# M_C_ext_main_cp2102N.net
KiCad netlist of a schematic drawn in EAGLE
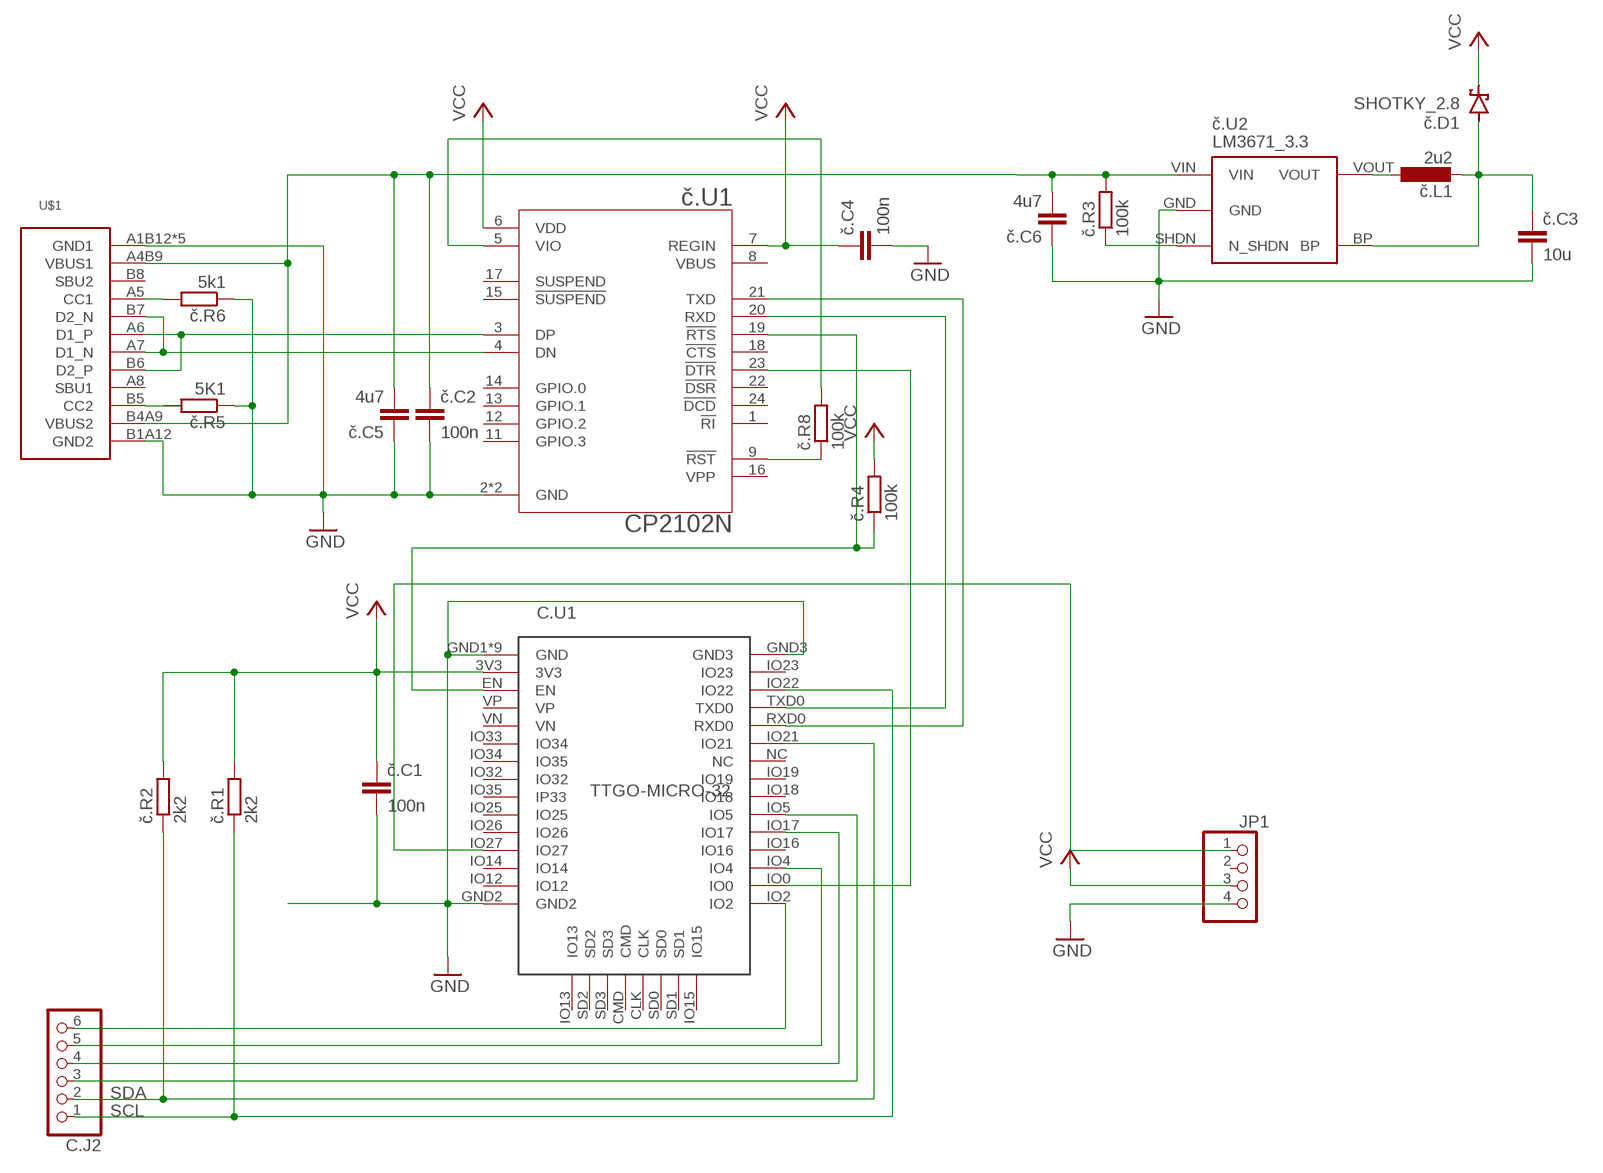
[diagram p0: schematic, sheet 1]

(export (version "E")
  (design (tool "Eeschema 10.0.6"))
  (components
    (comp (ref "C.J2")
      (value "PINHD-1X6")
      (footprint "eagle-import:1X06")
      (libsource (lib "eagle-import") (part "PINHD-1X6"))
    )
    (comp (ref "C.U1")
      (value "TTGO-MICRO-32")
      (footprint "eagle-import:TTGO-MICRO-32")
      (libsource (lib "eagle-import") (part "TTGO-MICRO-32"))
    )
    (comp (ref "JP1")
      (value "PINHD-1X4")
      (footprint "eagle-import:1X04")
      (libsource (lib "eagle-import") (part "PINHD-1X4"))
    )
    (comp (ref "U$1")
      (value "USB-C")
      (footprint "eagle-import:USB-C")
      (libsource (lib "eagle-import") (part "USB-C"))
    )
    (comp (ref "č.C1")
      (value "100n")
      (footprint "eagle-import:C0603")
      (libsource (lib "eagle-import") (part "C-EUC0603"))
    )
    (comp (ref "č.C2")
      (value "100n")
      (footprint "eagle-import:C0603")
      (libsource (lib "eagle-import") (part "C-EUC0603"))
    )
    (comp (ref "č.C3")
      (value "10u")
      (footprint "eagle-import:C0805")
      (libsource (lib "eagle-import") (part "C-EUC0805"))
    )
    (comp (ref "č.C4")
      (value "100n")
      (footprint "eagle-import:C0603")
      (libsource (lib "eagle-import") (part "C-EUC0603"))
    )
    (comp (ref "č.C5")
      (value "4u7")
      (footprint "eagle-import:C0603")
      (libsource (lib "eagle-import") (part "C-EUC0603"))
    )
    (comp (ref "č.C6")
      (value "4u7")
      (footprint "eagle-import:C0603")
      (libsource (lib "eagle-import") (part "C-EUC0603"))
    )
    (comp (ref "č.D1")
      (value "SHOTKY_2.8")
      (footprint "eagle-import:SHOTKY_2.8")
      (libsource (lib "eagle-import") (part "SHOTKY_2.8"))
    )
    (comp (ref "č.L1")
      (value "2u2")
      (footprint "eagle-import:L3230M")
      (libsource (lib "eagle-import") (part "L-EUL3230M"))
    )
    (comp (ref "č.R1")
      (value "2k2")
      (footprint "eagle-import:R0603")
      (libsource (lib "eagle-import") (part "R-EU_R0603"))
    )
    (comp (ref "č.R2")
      (value "2k2")
      (footprint "eagle-import:R0603")
      (libsource (lib "eagle-import") (part "R-EU_R0603"))
    )
    (comp (ref "č.R3")
      (value "100k")
      (footprint "eagle-import:R0603")
      (libsource (lib "eagle-import") (part "R-EU_R0603"))
    )
    (comp (ref "č.R4")
      (value "100k")
      (footprint "eagle-import:R0603")
      (libsource (lib "eagle-import") (part "R-EU_R0603"))
    )
    (comp (ref "č.R5")
      (value "5K1")
      (footprint "eagle-import:R0603")
      (libsource (lib "eagle-import") (part "R-EU_R0603"))
    )
    (comp (ref "č.R6")
      (value "5k1")
      (footprint "eagle-import:R0603")
      (libsource (lib "eagle-import") (part "R-EU_R0603"))
    )
    (comp (ref "č.R8")
      (value "100k")
      (footprint "eagle-import:R0603")
      (libsource (lib "eagle-import") (part "R-EU_R0603"))
    )
    (comp (ref "č.U1")
      (value "CP2102N")
      (footprint "eagle-import:QFN50P400X400X80-25N")
      (fields (field (name "MF") "Silicon Labs") (field (name "MP") "CP2104"))
      (libsource (lib "eagle-import") (part "CP2104-F03-GM"))
    )
    (comp (ref "č.U2")
      (value "LM3671_3.3")
      (footprint "eagle-import:SOT32-5")
      (libsource (lib "eagle-import") (part "STABILISER_APE8865"))
    )
  )
  (nets
    (net (code "1") (name "/SCL") (class "Default")
      (node (ref "C.J2") (pin "1") (pinfunction "1_1") (pintype "passive"))
      (node (ref "C.U1") (pin "IO22") (pinfunction "IO22_IO22") (pintype "bidirectional"))
      (node (ref "č.R1") (pin "1") (pinfunction "1_1") (pintype "passive"))
    )
    (net (code "2") (name "/SDA") (class "Default")
      (node (ref "C.J2") (pin "2") (pinfunction "2_2") (pintype "passive"))
      (node (ref "C.U1") (pin "IO21") (pinfunction "IO21_IO21") (pintype "bidirectional"))
      (node (ref "č.R2") (pin "1") (pinfunction "1_1") (pintype "passive"))
    )
    (net (code "3") (name "GND") (class "Default")
      (node (ref "C.U1") (pin "GND1") (pinfunction "GND_GND1") (pintype "power_in"))
      (node (ref "C.U1") (pin "GND10") (pinfunction "GND_GND10") (pintype "power_in"))
      (node (ref "C.U1") (pin "GND11") (pinfunction "GND_GND11") (pintype "power_in"))
      (node (ref "C.U1") (pin "GND2") (pinfunction "GND2_GND2") (pintype "power_in"))
      (node (ref "C.U1") (pin "GND3") (pinfunction "GND3_GND3") (pintype "power_in"))
      (node (ref "C.U1") (pin "GND4") (pinfunction "GND_GND4") (pintype "power_in"))
      (node (ref "C.U1") (pin "GND5") (pinfunction "GND_GND5") (pintype "power_in"))
      (node (ref "C.U1") (pin "GND6") (pinfunction "GND_GND6") (pintype "power_in"))
      (node (ref "C.U1") (pin "GND7") (pinfunction "GND_GND7") (pintype "power_in"))
      (node (ref "C.U1") (pin "GND8") (pinfunction "GND_GND8") (pintype "power_in"))
      (node (ref "C.U1") (pin "GND9") (pinfunction "GND_GND9") (pintype "power_in"))
      (node (ref "JP1") (pin "4") (pinfunction "4_4") (pintype "passive"))
      (node (ref "U$1") (pin "A1B12") (pinfunction "GND1_A1B12") (pintype "bidirectional"))
      (node (ref "U$1") (pin "B1A12") (pinfunction "GND2_B1A12") (pintype "bidirectional"))
      (node (ref "U$1") (pin "SH1") (pinfunction "GND1_SH1") (pintype "bidirectional"))
      (node (ref "U$1") (pin "SH2") (pinfunction "GND1_SH2") (pintype "bidirectional"))
      (node (ref "U$1") (pin "SH3") (pinfunction "GND1_SH3") (pintype "bidirectional"))
      (node (ref "U$1") (pin "SH4") (pinfunction "GND1_SH4") (pintype "bidirectional"))
      (node (ref "č.C1") (pin "2") (pinfunction "2_2") (pintype "passive"))
      (node (ref "č.C2") (pin "2") (pinfunction "2_2") (pintype "passive"))
      (node (ref "č.C3") (pin "2") (pinfunction "2_2") (pintype "passive"))
      (node (ref "č.C4") (pin "2") (pinfunction "2_2") (pintype "passive"))
      (node (ref "č.C5") (pin "1") (pinfunction "1_1") (pintype "passive"))
      (node (ref "č.C6") (pin "1") (pinfunction "1_1") (pintype "passive"))
      (node (ref "č.R5") (pin "1") (pinfunction "1_1") (pintype "passive"))
      (node (ref "č.R6") (pin "1") (pinfunction "1_1") (pintype "passive"))
      (node (ref "č.U1") (pin "2") (pinfunction "GND_2") (pintype "power_in"))
      (node (ref "č.U1") (pin "25") (pinfunction "GND_25") (pintype "power_in"))
      (node (ref "č.U2") (pin "GND") (pinfunction "GND_GND") (pintype "bidirectional"))
    )
    (net (code "4") (name "Net-(C.J2-Pad3)") (class "Default")
      (node (ref "C.J2") (pin "3") (pinfunction "3_3") (pintype "passive"))
      (node (ref "C.U1") (pin "IO5") (pinfunction "IO5_IO5") (pintype "bidirectional"))
    )
    (net (code "5") (name "Net-(C.J2-Pad4)") (class "Default")
      (node (ref "C.J2") (pin "4") (pinfunction "4_4") (pintype "passive"))
      (node (ref "C.U1") (pin "IO17") (pinfunction "IO17_IO17") (pintype "bidirectional"))
    )
    (net (code "6") (name "Net-(C.J2-Pad5)") (class "Default")
      (node (ref "C.J2") (pin "5") (pinfunction "5_5") (pintype "passive"))
      (node (ref "C.U1") (pin "IO4") (pinfunction "IO4_IO4") (pintype "bidirectional"))
    )
    (net (code "7") (name "Net-(C.J2-Pad6)") (class "Default")
      (node (ref "C.J2") (pin "6") (pinfunction "6_6") (pintype "passive"))
      (node (ref "C.U1") (pin "IO2") (pinfunction "IO2_IO2") (pintype "bidirectional"))
    )
    (net (code "8") (name "Net-(C.U1-PadIO27)") (class "Default")
      (node (ref "C.U1") (pin "IO27") (pinfunction "IO27_IO27") (pintype "bidirectional"))
      (node (ref "JP1") (pin "1") (pinfunction "1_1") (pintype "passive"))
    )
    (net (code "9") (name "Net-(U$1-CC1)") (class "Default")
      (node (ref "U$1") (pin "A5") (pinfunction "CC1_A5") (pintype "bidirectional"))
      (node (ref "č.R6") (pin "2") (pinfunction "2_2") (pintype "passive"))
    )
    (net (code "10") (name "Net-(U$1-CC2)") (class "Default")
      (node (ref "U$1") (pin "B5") (pinfunction "CC2_B5") (pintype "bidirectional"))
      (node (ref "č.R5") (pin "2") (pinfunction "2_2") (pintype "passive"))
    )
    (net (code "11") (name "Net-(U$1-D1_N)") (class "Default")
      (node (ref "U$1") (pin "A7") (pinfunction "D1_N_A7") (pintype "bidirectional"))
      (node (ref "U$1") (pin "B7") (pinfunction "D2_N_B7") (pintype "bidirectional"))
      (node (ref "č.U1") (pin "4") (pinfunction "DN_4") (pintype "bidirectional"))
    )
    (net (code "12") (name "Net-(U$1-D1_P)") (class "Default")
      (node (ref "U$1") (pin "A6") (pinfunction "D1_P_A6") (pintype "bidirectional"))
      (node (ref "U$1") (pin "B6") (pinfunction "D2_P_B6") (pintype "bidirectional"))
      (node (ref "č.U1") (pin "3") (pinfunction "DP_3") (pintype "bidirectional"))
    )
    (net (code "13") (name "Net-(U$1-VBUS1)") (class "Default")
      (node (ref "U$1") (pin "A4B9") (pinfunction "VBUS1_A4B9") (pintype "bidirectional"))
      (node (ref "U$1") (pin "B4A9") (pinfunction "VBUS2_B4A9") (pintype "bidirectional"))
      (node (ref "č.C2") (pin "1") (pinfunction "1_1") (pintype "passive"))
      (node (ref "č.C5") (pin "2") (pinfunction "2_2") (pintype "passive"))
      (node (ref "č.C6") (pin "2") (pinfunction "2_2") (pintype "passive"))
      (node (ref "č.R3") (pin "2") (pinfunction "2_2") (pintype "passive"))
      (node (ref "č.U2") (pin "VIN") (pinfunction "VIN_VIN") (pintype "bidirectional"))
    )
    (net (code "14") (name "Net-(č.C3-Pad1)") (class "Default")
      (node (ref "č.C3") (pin "1") (pinfunction "1_1") (pintype "passive"))
      (node (ref "č.D1") (pin "A") (pinfunction "A_A") (pintype "passive"))
      (node (ref "č.L1") (pin "2") (pinfunction "2_2") (pintype "passive"))
      (node (ref "č.U2") (pin "BP") (pinfunction "BP_BP") (pintype "bidirectional"))
    )
    (net (code "15") (name "Net-(č.L1-Pad1)") (class "Default")
      (node (ref "č.L1") (pin "1") (pinfunction "1_1") (pintype "passive"))
      (node (ref "č.U2") (pin "VOUT") (pinfunction "VOUT_VOUT") (pintype "bidirectional"))
    )
    (net (code "16") (name "Net-(č.U1-RXD)") (class "Default")
      (node (ref "C.U1") (pin "TXD0") (pinfunction "TXD0_TXD0") (pintype "bidirectional"))
      (node (ref "č.U1") (pin "20") (pinfunction "RXD_20") (pintype "input"))
    )
    (net (code "17") (name "Net-(č.U1-TXD)") (class "Default")
      (node (ref "C.U1") (pin "RXD0") (pinfunction "RXD0_RXD0") (pintype "bidirectional"))
      (node (ref "č.U1") (pin "21") (pinfunction "TXD_21") (pintype "output"))
    )
    (net (code "18") (name "Net-(č.U1-VIO)") (class "Default")
      (node (ref "č.R8") (pin "2") (pinfunction "2_2") (pintype "passive"))
      (node (ref "č.U1") (pin "5") (pinfunction "VIO_5") (pintype "power_in"))
    )
    (net (code "19") (name "Net-(č.U1-~{DTR})") (class "Default")
      (node (ref "C.U1") (pin "IO0") (pinfunction "IO0_IO0") (pintype "bidirectional"))
      (node (ref "č.U1") (pin "23") (pinfunction "~{DTR}_23") (pintype "output"))
    )
    (net (code "20") (name "Net-(č.U1-~{RST})") (class "Default")
      (node (ref "č.R8") (pin "1") (pinfunction "1_1") (pintype "passive"))
      (node (ref "č.U1") (pin "9") (pinfunction "~{RST}_9") (pintype "bidirectional"))
    )
    (net (code "21") (name "Net-(č.U1-~{RTS})") (class "Default")
      (node (ref "C.U1") (pin "EN") (pinfunction "EN_EN") (pintype "bidirectional"))
      (node (ref "č.R4") (pin "1") (pinfunction "1_1") (pintype "passive"))
      (node (ref "č.U1") (pin "19") (pinfunction "~{RTS}_19") (pintype "output"))
    )
    (net (code "22") (name "Net-(č.U2-N_SHDN)") (class "Default")
      (node (ref "č.R3") (pin "1") (pinfunction "1_1") (pintype "passive"))
      (node (ref "č.U2") (pin "SHDN") (pinfunction "N_SHDN_SHDN") (pintype "bidirectional"))
    )
    (net (code "23") (name "VCC") (class "Default")
      (node (ref "C.U1") (pin "3V3") (pinfunction "3V3_3V3") (pintype "power_in"))
      (node (ref "JP1") (pin "3") (pinfunction "3_3") (pintype "passive"))
      (node (ref "č.C1") (pin "1") (pinfunction "1_1") (pintype "passive"))
      (node (ref "č.C4") (pin "1") (pinfunction "1_1") (pintype "passive"))
      (node (ref "č.D1") (pin "K") (pinfunction "C_K") (pintype "passive"))
      (node (ref "č.R1") (pin "2") (pinfunction "2_2") (pintype "passive"))
      (node (ref "č.R2") (pin "2") (pinfunction "2_2") (pintype "passive"))
      (node (ref "č.R4") (pin "2") (pinfunction "2_2") (pintype "passive"))
      (node (ref "č.U1") (pin "6") (pinfunction "VDD_6") (pintype "power_in"))
      (node (ref "č.U1") (pin "7") (pinfunction "REGIN_7") (pintype "input"))
    )
    (net (code "24") (name "unconnected-(C.U1-IO34-PadIO33)") (class "Default")
      (node (ref "C.U1") (pin "IO33") (pinfunction "IO34_IO33") (pintype "bidirectional"))
    )
    (net (code "25") (name "unconnected-(C.U1-IO35-PadIO34)") (class "Default")
      (node (ref "C.U1") (pin "IO34") (pinfunction "IO35_IO34") (pintype "bidirectional"))
    )
    (net (code "26") (name "unconnected-(C.U1-IP33-PadIO35)") (class "Default")
      (node (ref "C.U1") (pin "IO35") (pinfunction "IP33_IO35") (pintype "bidirectional"))
    )
    (net (code "27") (name "unconnected-(C.U1-PadCLK)") (class "Default")
      (node (ref "C.U1") (pin "CLK") (pinfunction "CLK_CLK") (pintype "bidirectional"))
    )
    (net (code "28") (name "unconnected-(C.U1-PadCMD)") (class "Default")
      (node (ref "C.U1") (pin "CMD") (pinfunction "CMD_CMD") (pintype "bidirectional"))
    )
    (net (code "29") (name "unconnected-(C.U1-PadIO12)") (class "Default")
      (node (ref "C.U1") (pin "IO12") (pinfunction "IO12_IO12") (pintype "bidirectional"))
    )
    (net (code "30") (name "unconnected-(C.U1-PadIO13)") (class "Default")
      (node (ref "C.U1") (pin "IO13") (pinfunction "IO13_IO13") (pintype "bidirectional"))
    )
    (net (code "31") (name "unconnected-(C.U1-PadIO14)") (class "Default")
      (node (ref "C.U1") (pin "IO14") (pinfunction "IO14_IO14") (pintype "bidirectional"))
    )
    (net (code "32") (name "unconnected-(C.U1-PadIO15)") (class "Default")
      (node (ref "C.U1") (pin "IO15") (pinfunction "IO15_IO15") (pintype "bidirectional"))
    )
    (net (code "33") (name "unconnected-(C.U1-PadIO16)") (class "Default")
      (node (ref "C.U1") (pin "IO16") (pinfunction "IO16_IO16") (pintype "bidirectional"))
    )
    (net (code "34") (name "unconnected-(C.U1-PadIO18)") (class "Default")
      (node (ref "C.U1") (pin "IO18") (pinfunction "IO18_IO18") (pintype "bidirectional"))
    )
    (net (code "35") (name "unconnected-(C.U1-PadIO19)") (class "Default")
      (node (ref "C.U1") (pin "IO19") (pinfunction "IO19_IO19") (pintype "bidirectional"))
    )
    (net (code "36") (name "unconnected-(C.U1-PadIO23)") (class "Default")
      (node (ref "C.U1") (pin "IO23") (pinfunction "IO23_IO23") (pintype "bidirectional"))
    )
    (net (code "37") (name "unconnected-(C.U1-PadIO25)") (class "Default")
      (node (ref "C.U1") (pin "IO25") (pinfunction "IO25_IO25") (pintype "bidirectional"))
    )
    (net (code "38") (name "unconnected-(C.U1-PadIO26)") (class "Default")
      (node (ref "C.U1") (pin "IO26") (pinfunction "IO26_IO26") (pintype "bidirectional"))
    )
    (net (code "39") (name "unconnected-(C.U1-PadIO32)") (class "Default")
      (node (ref "C.U1") (pin "IO32") (pinfunction "IO32_IO32") (pintype "bidirectional"))
    )
    (net (code "40") (name "unconnected-(C.U1-PadNC)") (class "Default")
      (node (ref "C.U1") (pin "NC") (pinfunction "NC_NC") (pintype "no_connect"))
    )
    (net (code "41") (name "unconnected-(C.U1-PadSD0)") (class "Default")
      (node (ref "C.U1") (pin "SD0") (pinfunction "SD0_SD0") (pintype "bidirectional"))
    )
    (net (code "42") (name "unconnected-(C.U1-PadSD1)") (class "Default")
      (node (ref "C.U1") (pin "SD1") (pinfunction "SD1_SD1") (pintype "bidirectional"))
    )
    (net (code "43") (name "unconnected-(C.U1-PadSD2)") (class "Default")
      (node (ref "C.U1") (pin "SD2") (pinfunction "SD2_SD2") (pintype "bidirectional"))
    )
    (net (code "44") (name "unconnected-(C.U1-PadSD3)") (class "Default")
      (node (ref "C.U1") (pin "SD3") (pinfunction "SD3_SD3") (pintype "bidirectional"))
    )
    (net (code "45") (name "unconnected-(C.U1-PadVN)") (class "Default")
      (node (ref "C.U1") (pin "VN") (pinfunction "VN_VN") (pintype "bidirectional"))
    )
    (net (code "46") (name "unconnected-(C.U1-PadVP)") (class "Default")
      (node (ref "C.U1") (pin "VP") (pinfunction "VP_VP") (pintype "bidirectional"))
    )
    (net (code "47") (name "unconnected-(JP1-Pad2)") (class "Default")
      (node (ref "JP1") (pin "2") (pinfunction "2_2") (pintype "passive"))
    )
    (net (code "48") (name "unconnected-(U$1-SBU1-PadA8)") (class "Default")
      (node (ref "U$1") (pin "A8") (pinfunction "SBU1_A8") (pintype "bidirectional"))
    )
    (net (code "49") (name "unconnected-(U$1-SBU2-PadB8)") (class "Default")
      (node (ref "U$1") (pin "B8") (pinfunction "SBU2_B8") (pintype "bidirectional"))
    )
    (net (code "50") (name "unconnected-(č.U1-GPIO.0-Pad14)") (class "Default")
      (node (ref "č.U1") (pin "14") (pinfunction "GPIO.0_14") (pintype "bidirectional"))
    )
    (net (code "51") (name "unconnected-(č.U1-GPIO.1-Pad13)") (class "Default")
      (node (ref "č.U1") (pin "13") (pinfunction "GPIO.1_13") (pintype "bidirectional"))
    )
    (net (code "52") (name "unconnected-(č.U1-GPIO.2-Pad12)") (class "Default")
      (node (ref "č.U1") (pin "12") (pinfunction "GPIO.2_12") (pintype "bidirectional"))
    )
    (net (code "53") (name "unconnected-(č.U1-GPIO.3-Pad11)") (class "Default")
      (node (ref "č.U1") (pin "11") (pinfunction "GPIO.3_11") (pintype "bidirectional"))
    )
    (net (code "54") (name "unconnected-(č.U1-SUSPEND-Pad17)") (class "Default")
      (node (ref "č.U1") (pin "17") (pinfunction "SUSPEND_17") (pintype "output"))
    )
    (net (code "55") (name "unconnected-(č.U1-VBUS-Pad8)") (class "Default")
      (node (ref "č.U1") (pin "8") (pinfunction "VBUS_8") (pintype "input"))
    )
    (net (code "56") (name "unconnected-(č.U1-VPP-Pad16)") (class "Default")
      (node (ref "č.U1") (pin "16") (pinfunction "VPP_16") (pintype "passive"))
    )
    (net (code "57") (name "unconnected-(č.U1-~{CTS}-Pad18)") (class "Default")
      (node (ref "č.U1") (pin "18") (pinfunction "~{CTS}_18") (pintype "input"))
    )
    (net (code "58") (name "unconnected-(č.U1-~{DCD}-Pad24)") (class "Default")
      (node (ref "č.U1") (pin "24") (pinfunction "~{DCD}_24") (pintype "input"))
    )
    (net (code "59") (name "unconnected-(č.U1-~{DSR}-Pad22)") (class "Default")
      (node (ref "č.U1") (pin "22") (pinfunction "~{DSR}_22") (pintype "input"))
    )
    (net (code "60") (name "unconnected-(č.U1-~{RI}-Pad1)") (class "Default")
      (node (ref "č.U1") (pin "1") (pinfunction "~{RI}_1") (pintype "input"))
    )
    (net (code "61") (name "unconnected-(č.U1-~{SUSPEND}-Pad15)") (class "Default")
      (node (ref "č.U1") (pin "15") (pinfunction "~{SUSPEND}_15") (pintype "output"))
    )
  )
)
